# power-input.net
KiCad netlist of a schematic drawn in Altium Designer
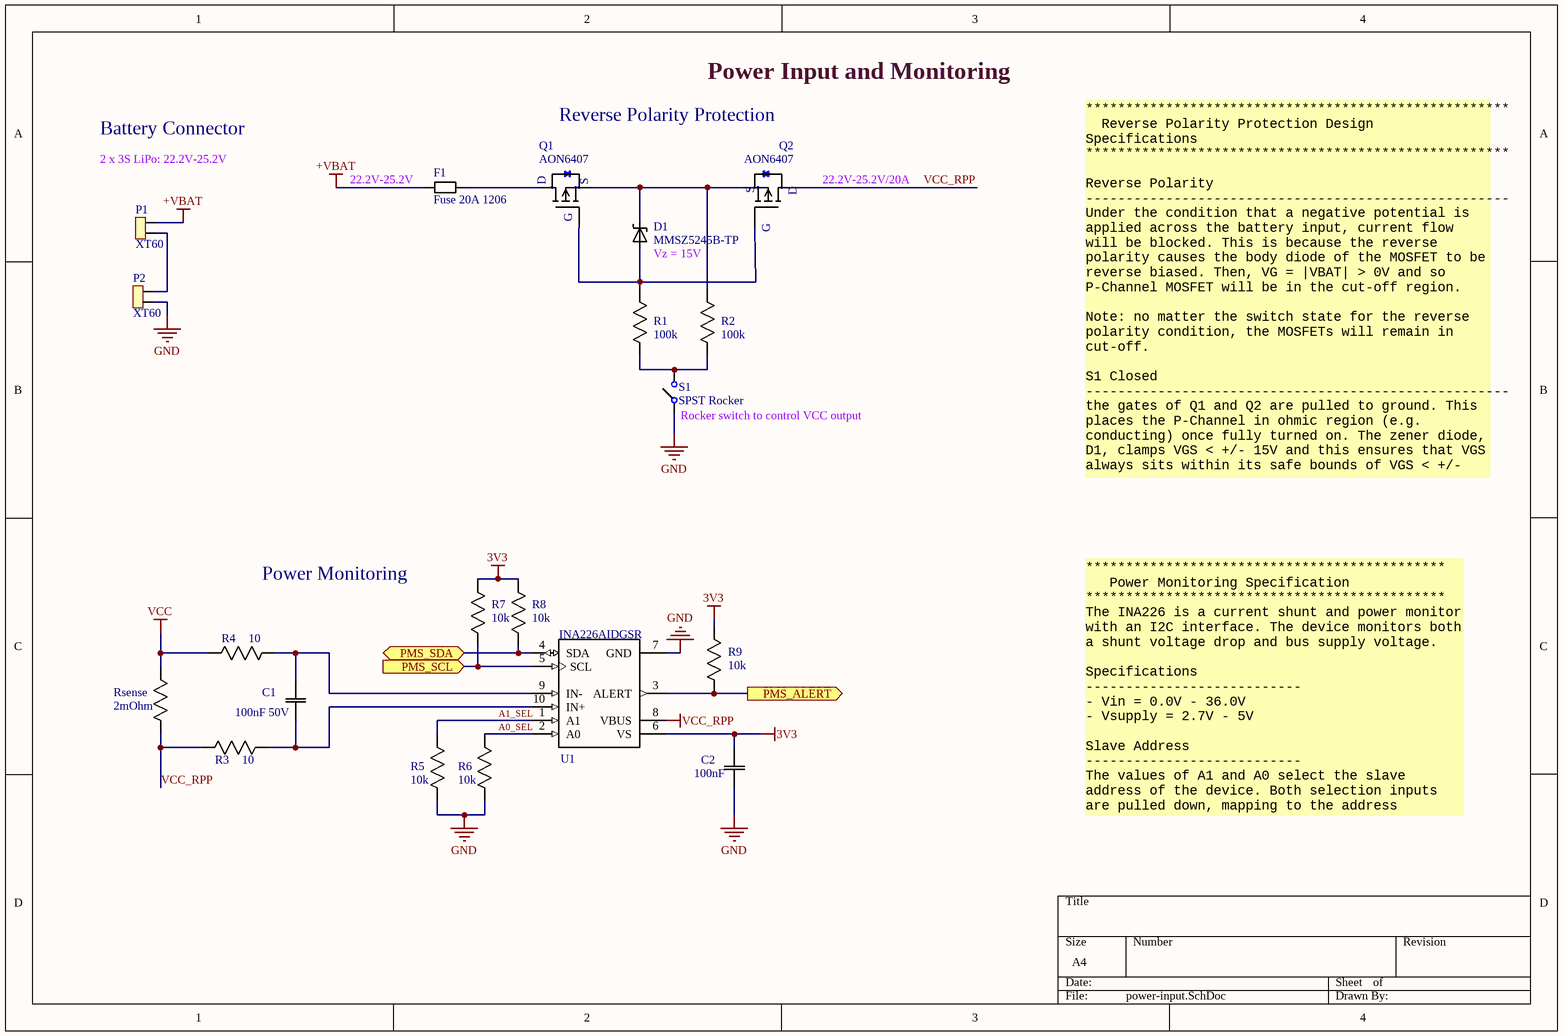
[diagram p0: power-input.SchDoc]

(export (version "E")
  (design (tool "Eeschema 10.0.6"))
  (components
    (comp (ref "C1")
      (value "100nF 50V")
      (footprint "0805")
      (description "CAP CER 0.1UF 50V X7R 0805")
      (fields (field (name "MP") "CC0805KRX7R9BB104") (field (name "MF") "Yageo"))
      (libsource (lib "AltiumLibraries") (part "CAP 100nF 0805"))
    )
    (comp (ref "C2")
      (value "100nF")
      (footprint "0805")
      (description "CAP CER 0.1UF 50V X7R 0805")
      (fields (field (name "MP") "CC0805KRX7R9BB104") (field (name "MF") "Yageo"))
      (libsource (lib "AltiumLibraries") (part "CAP 100nF 0805"))
    )
    (comp (ref "D1")
      (value "MMSZ5245B-TP")
      (footprint "SOD-123")
      (description "Zener Diode 15V 500mW ±5% Surface Mount SOD-123")
      (fields (field (name "MP") "MMSZ5224BT1G") (field (name "MF") "ON Semiconductor"))
      (libsource (lib "AltiumLibraries") (part "MMSZ5245B-TP"))
    )
    (comp (ref "F1")
      (value "Fuse 20A 1206")
      (footprint "1206")
      (description "FUSE BOARD MOUNT 20A 32VAC 63VDC")
      (fields (field (name "MF") "Schurter Inc.") (field (name "MP") "3413.0331.22"))
      (libsource (lib "AltiumLibraries") (part "Fuse 20A 1206"))
    )
    (comp (ref "P1")
      (value "XT60")
      (footprint "XT60Connector")
      (description "XT60 CONNECTORS FEMALE PAIR")
      (fields (field (name "MF") "SparkFun Electronics") (field (name "MP") "PRT-10474"))
      (libsource (lib "AltiumLibraries") (part "XT60 Connector"))
    )
    (comp (ref "P2")
      (value "XT60")
      (footprint "XT60Connector")
      (description "XT60 CONNECTORS FEMALE PAIR")
      (fields (field (name "MF") "SparkFun Electronics") (field (name "MP") "PRT-10474"))
      (libsource (lib "AltiumLibraries") (part "XT60 Connector"))
    )
    (comp (ref "Q1")
      (value "AON6407")
      (footprint "8-PowerSMD")
      (description "P-Channel 30V 32A (Ta), 85A (Tc) 7.3W (Ta), 83W (Tc) Surface Mount 8-DFN (5x6)")
      (fields (field (name "MF") "Alpha & Omega Semiconductor Inc."))
      (libsource (lib "AltiumLibraries") (part "AON6407"))
    )
    (comp (ref "Q2")
      (value "AON6407")
      (footprint "8-PowerSMD")
      (description "P-Channel 30V 32A (Ta), 85A (Tc) 7.3W (Ta), 83W (Tc) Surface Mount 8-DFN (5x6)")
      (fields (field (name "MF") "Alpha & Omega Semiconductor Inc."))
      (libsource (lib "AltiumLibraries") (part "AON6407"))
    )
    (comp (ref "R1")
      (value "100k")
      (footprint "0805")
      (description "RES SMD 100K OHM 1% 1/8W 0805")
      (fields (field (name "MP") "RC0805FR-07100KL") (field (name "MF") "Yageo"))
      (libsource (lib "AltiumLibraries") (part "RES 100k 0805"))
    )
    (comp (ref "R2")
      (value "100k")
      (footprint "0805")
      (description "RES SMD 100K OHM 1% 1/8W 0805")
      (fields (field (name "MP") "RC0805FR-07100KL") (field (name "MF") "Yageo"))
      (libsource (lib "AltiumLibraries") (part "RES 100k 0805"))
    )
    (comp (ref "R3")
      (value "10")
      (footprint "0805")
      (description "RES SMD 10 OHM 1% 1/8W 0805")
      (fields (field (name "MP") "RC0805FR-0710RL") (field (name "MF") "Yageo"))
      (libsource (lib "AltiumLibraries") (part "RES 10 0805"))
    )
    (comp (ref "R4")
      (value "10")
      (footprint "0805")
      (description "RES SMD 10 OHM 1% 1/8W 0805")
      (fields (field (name "MP") "RC0805FR-0710RL") (field (name "MF") "Yageo"))
      (libsource (lib "AltiumLibraries") (part "RES 10 0805"))
    )
    (comp (ref "R5")
      (value "10k")
      (footprint "0805")
      (description "RES SMD 10K OHM 1% 1/8W 0805")
      (fields (field (name "TOLERANCE") "1%"))
      (libsource (lib "AltiumLibraries") (part "RES 10k 1/8W"))
    )
    (comp (ref "R6")
      (value "10k")
      (footprint "0805")
      (description "RES SMD 10K OHM 1% 1/8W 0805")
      (fields (field (name "TOLERANCE") "1%"))
      (libsource (lib "AltiumLibraries") (part "RES 10k 1/8W"))
    )
    (comp (ref "R7")
      (value "10k")
      (footprint "0805")
      (description "RES SMD 10K OHM 1% 1/8W 0805")
      (fields (field (name "MP") "RC0805FR-0710KL") (field (name "MF") "Yageo"))
      (libsource (lib "AltiumLibraries") (part "RES 10k 0805"))
    )
    (comp (ref "R8")
      (value "10k")
      (footprint "0805")
      (description "RES SMD 10K OHM 1% 1/8W 0805")
      (fields (field (name "MP") "RC0805FR-0710KL") (field (name "MF") "Yageo"))
      (libsource (lib "AltiumLibraries") (part "RES 10k 0805"))
    )
    (comp (ref "R9")
      (value "10k")
      (footprint "0805")
      (description "RES SMD 10K OHM 1% 1/8W 0805")
      (fields (field (name "MP") "RC0805FR-0710KL") (field (name "MF") "Yageo"))
      (libsource (lib "AltiumLibraries") (part "RES 10k 0805"))
    )
    (comp (ref "Rsense")
      (value "2mOhm")
      (footprint "1206")
      (description "RES 0.002 OHM 1% 1W 1206")
      (fields (field (name "MP") "CSR1206-0R002F1") (field (name "MF") "Riedon"))
      (libsource (lib "AltiumLibraries") (part "RES 2mOhm 1206"))
    )
    (comp (ref "S1")
      (value "SPST Rocker")
      (footprint "SWITCH ROCKER SPST 10A 125V")
      (description "Rocker Switch SPST 10A (AC) 125V Panel Mount, Snap-In")
      (fields (field (name "MP") "SRB22A2FBBNN") (field (name "MF") "ZF Electronics"))
      (libsource (lib "AltiumLibraries") (part "SWITCH ROCKER SPST 10A 125V"))
    )
    (comp (ref "U1")
      (value "INA226AIDGSR")
      (footprint "10-VSSOP")
      (fields (field (name "MF") "Texas Instruments"))
      (libsource (lib "AltiumLibraries") (part "INA226AIDGSR"))
    )
  )
  (nets
    (net (code "1") (name "+VBAT") (class "Default")
      (node (ref "F1") (pin "1") (pinfunction "1_1") (pintype "passive"))
      (node (ref "P1") (pin "2") (pinfunction "2_2") (pintype "passive"))
    )
    (net (code "2") (name "/A0_SEL") (class "Default")
      (node (ref "R6") (pin "1") (pinfunction "R1_1") (pintype "passive"))
      (node (ref "U1") (pin "2") (pinfunction "A0_2") (pintype "input"))
    )
    (net (code "3") (name "/A1_SEL") (class "Default")
      (node (ref "R5") (pin "1") (pinfunction "R1_1") (pintype "passive"))
      (node (ref "U1") (pin "1") (pinfunction "A1_1") (pintype "input"))
    )
    (net (code "4") (name "/PMS_ALERT") (class "Default")
      (node (ref "R9") (pin "2") (pinfunction "R2_2") (pintype "passive"))
      (node (ref "U1") (pin "3") (pinfunction "ALERT_3") (pintype "output"))
    )
    (net (code "5") (name "/PMS_SCL") (class "Default")
      (node (ref "R7") (pin "2") (pinfunction "R2_2") (pintype "passive"))
      (node (ref "U1") (pin "5") (pinfunction "SCL_5") (pintype "input"))
    )
    (net (code "6") (name "/PMS_SDA") (class "Default")
      (node (ref "R8") (pin "2") (pinfunction "R2_2") (pintype "passive"))
      (node (ref "U1") (pin "4") (pinfunction "SDA_4") (pintype "bidirectional"))
    )
    (net (code "7") (name "3V3") (class "Default")
      (node (ref "C2") (pin "2") (pinfunction "C2_2") (pintype "passive"))
      (node (ref "R7") (pin "1") (pinfunction "R1_1") (pintype "passive"))
      (node (ref "R8") (pin "1") (pinfunction "R1_1") (pintype "passive"))
      (node (ref "R9") (pin "1") (pinfunction "R1_1") (pintype "passive"))
      (node (ref "U1") (pin "6") (pinfunction "VS_6") (pintype "power_in"))
    )
    (net (code "8") (name "GND") (class "Default")
      (node (ref "C2") (pin "1") (pinfunction "C1_1") (pintype "passive"))
      (node (ref "P2") (pin "1") (pinfunction "1_1") (pintype "passive"))
      (node (ref "R5") (pin "2") (pinfunction "R2_2") (pintype "passive"))
      (node (ref "R6") (pin "2") (pinfunction "R2_2") (pintype "passive"))
      (node (ref "S1") (pin "0") (pinfunction "0_0") (pintype "passive"))
      (node (ref "U1") (pin "7") (pinfunction "GND_7") (pintype "power_in"))
    )
    (net (code "9") (name "Net-(C1-C1)") (class "Default")
      (node (ref "C1") (pin "1") (pinfunction "C1_1") (pintype "passive"))
      (node (ref "R3") (pin "1") (pinfunction "R1_1") (pintype "passive"))
      (node (ref "U1") (pin "10") (pinfunction "IN+_10") (pintype "input"))
    )
    (net (code "10") (name "Net-(C1-C2)") (class "Default")
      (node (ref "C1") (pin "2") (pinfunction "C2_2") (pintype "passive"))
      (node (ref "R4") (pin "1") (pinfunction "R1_1") (pintype "passive"))
      (node (ref "U1") (pin "9") (pinfunction "IN-_9") (pintype "input"))
    )
    (net (code "11") (name "Net-(F1-Pad2)") (class "Default")
      (node (ref "F1") (pin "2") (pinfunction "2_2") (pintype "passive"))
      (node (ref "Q1") (pin "D") (pinfunction "D_D") (pintype "passive"))
    )
    (net (code "12") (name "Net-(P1-Pad1)") (class "Default")
      (node (ref "P1") (pin "1") (pinfunction "1_1") (pintype "passive"))
      (node (ref "P2") (pin "2") (pinfunction "2_2") (pintype "passive"))
    )
    (net (code "13") (name "Net-(R1-R1)") (class "Default")
      (node (ref "D1") (pin "A") (pinfunction "A_A") (pintype "passive"))
      (node (ref "Q1") (pin "G") (pinfunction "G_G") (pintype "passive"))
      (node (ref "Q2") (pin "G") (pinfunction "G_G") (pintype "passive"))
      (node (ref "R1") (pin "1") (pinfunction "R1_1") (pintype "passive"))
    )
    (net (code "14") (name "Net-(R1-R2)") (class "Default")
      (node (ref "R1") (pin "2") (pinfunction "R2_2") (pintype "passive"))
      (node (ref "R2") (pin "2") (pinfunction "R2_2") (pintype "passive"))
      (node (ref "S1") (pin "1") (pinfunction "1_1") (pintype "passive"))
    )
    (net (code "15") (name "Net-(R2-R1)") (class "Default")
      (node (ref "D1") (pin "C") (pinfunction "C_C") (pintype "passive"))
      (node (ref "Q1") (pin "S") (pinfunction "S_S") (pintype "passive"))
      (node (ref "Q2") (pin "S") (pinfunction "S_S") (pintype "passive"))
      (node (ref "R2") (pin "1") (pinfunction "R1_1") (pintype "passive"))
    )
    (net (code "16") (name "VCC") (class "Default")
      (node (ref "R4") (pin "2") (pinfunction "R2_2") (pintype "passive"))
      (node (ref "Rsense") (pin "1") (pinfunction "R1_1") (pintype "passive"))
    )
    (net (code "17") (name "VCC_RPP") (class "Default")
      (node (ref "Q2") (pin "D") (pinfunction "D_D") (pintype "passive"))
      (node (ref "R3") (pin "2") (pinfunction "R2_2") (pintype "passive"))
      (node (ref "Rsense") (pin "2") (pinfunction "R2_2") (pintype "passive"))
      (node (ref "U1") (pin "8") (pinfunction "VBUS_8") (pintype "power_in"))
    )
  )
)
